# radiomic.net
KiCad netlist of a schematic drawn in Altium Designer
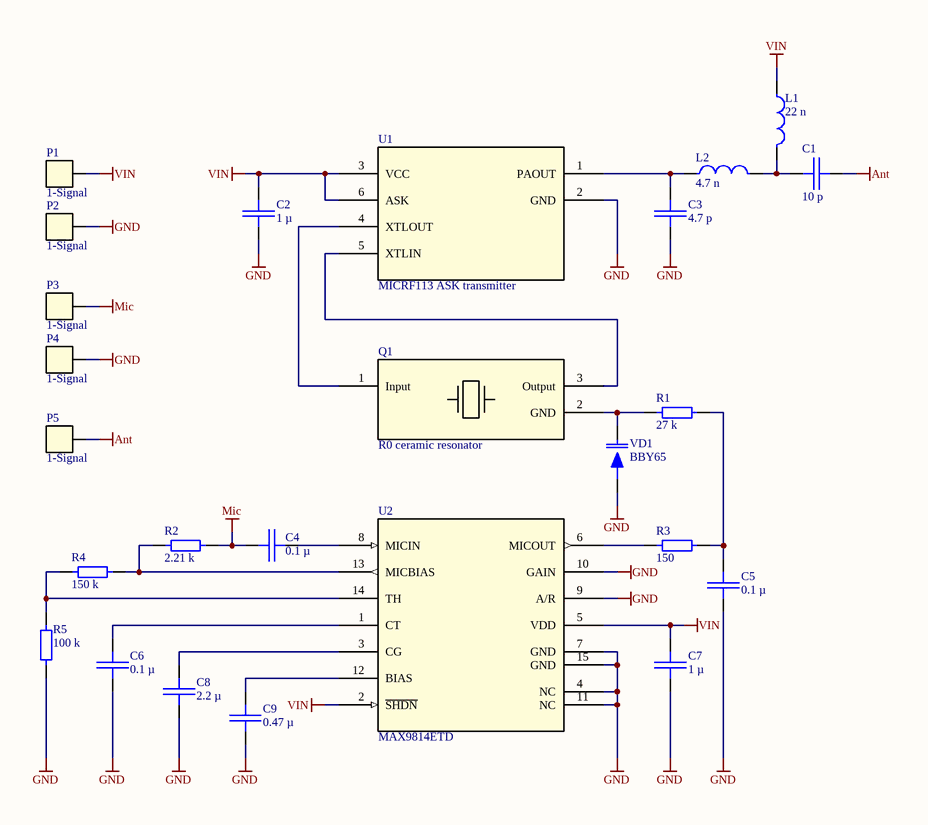
[diagram p0: radiomic.SchDoc]

(export (version "E")
  (design (tool "Eeschema 10.0.6"))
  (components
    (comp (ref "C1") (value "10 p") (footprint "0402") (libsource (lib "AltiumDesigner") (part "Cap")))
    (comp (ref "C2") (value "1 µ") (footprint "0402") (libsource (lib "AltiumDesigner") (part "Cap")))
    (comp (ref "C3") (value "4.7 p") (footprint "0402") (libsource (lib "AltiumDesigner") (part "Cap")))
    (comp (ref "C4") (value "0.1 µ") (footprint "0402") (libsource (lib "AltiumDesigner") (part "Cap")))
    (comp (ref "C5") (value "0.1 µ") (footprint "0402") (libsource (lib "AltiumDesigner") (part "Cap")))
    (comp (ref "C6") (value "0.1 µ") (footprint "0402") (libsource (lib "AltiumDesigner") (part "Cap")))
    (comp (ref "C7") (value "1 µ") (footprint "0402") (libsource (lib "AltiumDesigner") (part "Cap")))
    (comp (ref "C8") (value "2.2 µ") (footprint "0402") (libsource (lib "AltiumDesigner") (part "Cap")))
    (comp (ref "C9") (value "0.47 µ") (footprint "0402") (libsource (lib "AltiumDesigner") (part "Cap")))
    (comp (ref "L1") (value "22 n") (footprint "0402") (libsource (lib "AltiumDesigner") (part "Ind")))
    (comp (ref "L2") (value "4.7 n") (footprint "0402") (libsource (lib "AltiumDesigner") (part "Ind")))
    (comp (ref "P1")
      (value "1-Signal")
      (footprint "1-SignalSmall")
      (libsource (lib "AltiumDesigner") (part "1-Signal"))
    )
    (comp (ref "P2")
      (value "1-Signal")
      (footprint "1-SignalSmall")
      (libsource (lib "AltiumDesigner") (part "1-Signal"))
    )
    (comp (ref "P3")
      (value "1-Signal")
      (footprint "1-SignalSmall")
      (libsource (lib "AltiumDesigner") (part "1-Signal"))
    )
    (comp (ref "P4")
      (value "1-Signal")
      (footprint "1-SignalSmall")
      (libsource (lib "AltiumDesigner") (part "1-Signal"))
    )
    (comp (ref "P5")
      (value "1-Signal")
      (footprint "1-SignalSmall")
      (libsource (lib "AltiumDesigner") (part "1-Signal"))
    )
    (comp (ref "Q1")
      (value "R0 ceramic resonator")
      (footprint "R0")
      (libsource (lib "AltiumDesigner") (part "R0 resonator"))
    )
    (comp (ref "R1") (value "27 k") (footprint "0402") (libsource (lib "AltiumDesigner") (part "Res")))
    (comp (ref "R2") (value "2.21 k") (footprint "0402") (libsource (lib "AltiumDesigner") (part "Res")))
    (comp (ref "R3") (value "150") (footprint "0402") (libsource (lib "AltiumDesigner") (part "Res")))
    (comp (ref "R4") (value "150 k") (footprint "0402") (libsource (lib "AltiumDesigner") (part "Res")))
    (comp (ref "R5") (value "100 k") (footprint "0402") (libsource (lib "AltiumDesigner") (part "Res")))
    (comp (ref "U1")
      (value "MICRF113 ASK transmitter")
      (footprint "SOT23-6")
      (libsource (lib "AltiumDesigner") (part "MICRF113"))
    )
    (comp (ref "U2")
      (value "MAX9814ETD")
      (footprint "SON40P300X300X80-15N")
      (libsource (lib "AltiumDesigner") (part "MAX9814ETD"))
    )
    (comp (ref "VD1") (value "BBY65") (footprint "SC79") (libsource (lib "AltiumDesigner") (part "BBY65")))
  )
  (nets
    (net (code "1") (name "Ant") (class "Default")
      (node (ref "C1") (pin "2") (pinfunction "2_2") (pintype "passive"))
      (node (ref "P5") (pin "1") (pinfunction "1_1") (pintype "passive"))
    )
    (net (code "2") (name "GND") (class "Default")
      (node (ref "C2") (pin "1") (pinfunction "1_1") (pintype "passive"))
      (node (ref "C3") (pin "1") (pinfunction "1_1") (pintype "passive"))
      (node (ref "C5") (pin "1") (pinfunction "1_1") (pintype "passive"))
      (node (ref "C6") (pin "1") (pinfunction "1_1") (pintype "passive"))
      (node (ref "C7") (pin "1") (pinfunction "1_1") (pintype "passive"))
      (node (ref "C8") (pin "1") (pinfunction "1_1") (pintype "passive"))
      (node (ref "C9") (pin "1") (pinfunction "1_1") (pintype "passive"))
      (node (ref "P2") (pin "1") (pinfunction "1_1") (pintype "passive"))
      (node (ref "P4") (pin "1") (pinfunction "1_1") (pintype "passive"))
      (node (ref "R5") (pin "1") (pinfunction "1_1") (pintype "passive"))
      (node (ref "U1") (pin "2") (pinfunction "GND_2") (pintype "power_in"))
      (node (ref "U2") (pin "10") (pinfunction "GAIN_10") (pintype "passive"))
      (node (ref "U2") (pin "11") (pinfunction "NC_11") (pintype "passive"))
      (node (ref "U2") (pin "15") (pinfunction "GND_15") (pintype "power_in"))
      (node (ref "U2") (pin "4") (pinfunction "NC_4") (pintype "passive"))
      (node (ref "U2") (pin "7") (pinfunction "GND_7") (pintype "power_in"))
      (node (ref "U2") (pin "9") (pinfunction "A/R_9") (pintype "passive"))
      (node (ref "VD1") (pin "1") (pinfunction "A_1") (pintype "passive"))
    )
    (net (code "3") (name "Mic") (class "Default")
      (node (ref "C4") (pin "2") (pinfunction "2_2") (pintype "passive"))
      (node (ref "P3") (pin "1") (pinfunction "1_1") (pintype "passive"))
      (node (ref "R2") (pin "2") (pinfunction "2_2") (pintype "passive"))
    )
    (net (code "4") (name "Net-(C1-Pad1)") (class "Default")
      (node (ref "C1") (pin "1") (pinfunction "1_1") (pintype "passive"))
      (node (ref "L1") (pin "2") (pinfunction "2_2") (pintype "passive"))
      (node (ref "L2") (pin "2") (pinfunction "2_2") (pintype "passive"))
    )
    (net (code "5") (name "Net-(C5-Pad2)") (class "Default")
      (node (ref "C5") (pin "2") (pinfunction "2_2") (pintype "passive"))
      (node (ref "R1") (pin "2") (pinfunction "2_2") (pintype "passive"))
      (node (ref "R3") (pin "2") (pinfunction "2_2") (pintype "passive"))
    )
    (net (code "6") (name "Net-(Q1-GND)") (class "Default")
      (node (ref "Q1") (pin "2") (pinfunction "GND_2") (pintype "passive"))
      (node (ref "R1") (pin "1") (pinfunction "1_1") (pintype "passive"))
      (node (ref "VD1") (pin "2") (pinfunction "K_2") (pintype "passive"))
    )
    (net (code "7") (name "Net-(Q1-Input)") (class "Default")
      (node (ref "Q1") (pin "1") (pinfunction "Input_1") (pintype "passive"))
      (node (ref "U1") (pin "4") (pinfunction "XTLOUT_4") (pintype "passive"))
    )
    (net (code "8") (name "Net-(Q1-Output)") (class "Default")
      (node (ref "Q1") (pin "3") (pinfunction "Output_3") (pintype "passive"))
      (node (ref "U1") (pin "5") (pinfunction "XTLIN_5") (pintype "passive"))
    )
    (net (code "9") (name "Net-(U1-PAOUT)") (class "Default")
      (node (ref "C3") (pin "2") (pinfunction "2_2") (pintype "passive"))
      (node (ref "L2") (pin "1") (pinfunction "1_1") (pintype "passive"))
      (node (ref "U1") (pin "1") (pinfunction "PAOUT_1") (pintype "passive"))
    )
    (net (code "10") (name "Net-(U2-BIAS)") (class "Default")
      (node (ref "C9") (pin "2") (pinfunction "2_2") (pintype "passive"))
      (node (ref "U2") (pin "12") (pinfunction "BIAS_12") (pintype "passive"))
    )
    (net (code "11") (name "Net-(U2-CG)") (class "Default")
      (node (ref "C8") (pin "2") (pinfunction "2_2") (pintype "passive"))
      (node (ref "U2") (pin "3") (pinfunction "CG_3") (pintype "passive"))
    )
    (net (code "12") (name "Net-(U2-CT)") (class "Default")
      (node (ref "C6") (pin "2") (pinfunction "2_2") (pintype "passive"))
      (node (ref "U2") (pin "1") (pinfunction "CT_1") (pintype "passive"))
    )
    (net (code "13") (name "Net-(U2-MICBIAS)") (class "Default")
      (node (ref "R2") (pin "1") (pinfunction "1_1") (pintype "passive"))
      (node (ref "R4") (pin "2") (pinfunction "2_2") (pintype "passive"))
      (node (ref "U2") (pin "13") (pinfunction "MICBIAS_13") (pintype "output"))
    )
    (net (code "14") (name "Net-(U2-MICIN)") (class "Default")
      (node (ref "C4") (pin "1") (pinfunction "1_1") (pintype "passive"))
      (node (ref "U2") (pin "8") (pinfunction "MICIN_8") (pintype "input"))
    )
    (net (code "15") (name "Net-(U2-MICOUT)") (class "Default")
      (node (ref "R3") (pin "1") (pinfunction "1_1") (pintype "passive"))
      (node (ref "U2") (pin "6") (pinfunction "MICOUT_6") (pintype "output"))
    )
    (net (code "16") (name "Net-(U2-TH)") (class "Default")
      (node (ref "R4") (pin "1") (pinfunction "1_1") (pintype "passive"))
      (node (ref "R5") (pin "2") (pinfunction "2_2") (pintype "passive"))
      (node (ref "U2") (pin "14") (pinfunction "TH_14") (pintype "passive"))
    )
    (net (code "17") (name "VIN") (class "Default")
      (node (ref "C2") (pin "2") (pinfunction "2_2") (pintype "passive"))
      (node (ref "C7") (pin "2") (pinfunction "2_2") (pintype "passive"))
      (node (ref "L1") (pin "1") (pinfunction "1_1") (pintype "passive"))
      (node (ref "P1") (pin "1") (pinfunction "1_1") (pintype "passive"))
      (node (ref "U1") (pin "3") (pinfunction "VCC_3") (pintype "power_in"))
      (node (ref "U1") (pin "6") (pinfunction "ASK_6") (pintype "passive"))
      (node (ref "U2") (pin "2") (pinfunction "~{SHDN}_2") (pintype "input"))
      (node (ref "U2") (pin "5") (pinfunction "VDD_5") (pintype "power_in"))
    )
  )
)
